# ssslidar_v1_0_main_board.net
KiCad netlist of a schematic drawn in EAGLE
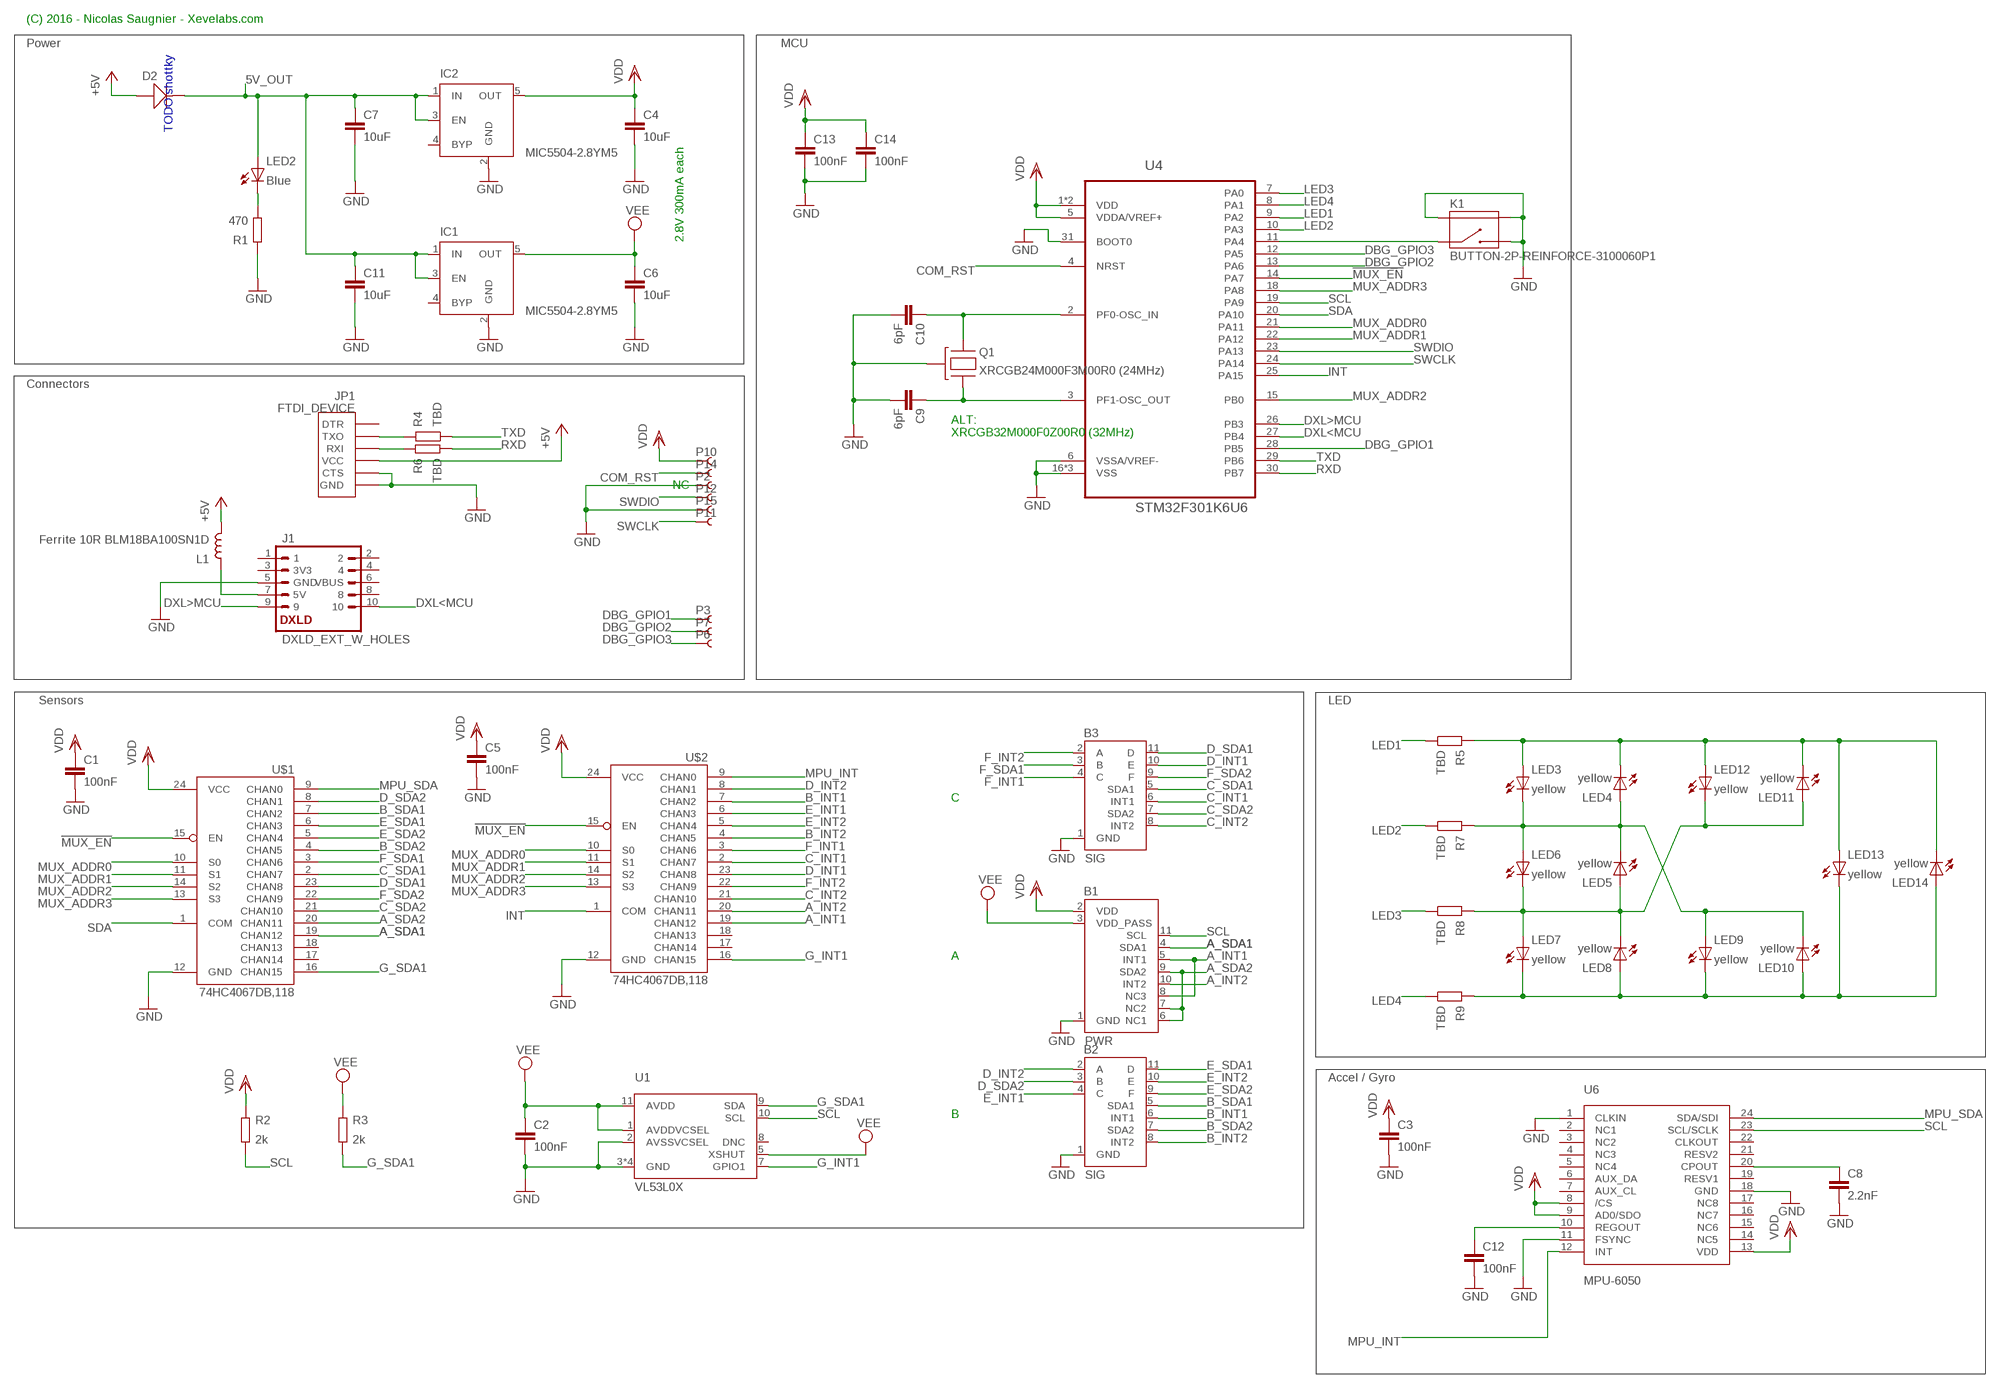
[diagram p0: schematic, sheet 1]

(export (version "E")
  (design (tool "Eeschema 10.0.6"))
  (components
    (comp (ref "B1")
      (value "PWR")
      (footprint "eagle-import:BLADE")
      (libsource (lib "eagle-import") (part "BLADE_PWR_BOTTOM"))
    )
    (comp (ref "B2")
      (value "SIG")
      (footprint "eagle-import:BLADE")
      (libsource (lib "eagle-import") (part "BLADE_SIG_BOTTOM"))
    )
    (comp (ref "B3")
      (value "SIG")
      (footprint "eagle-import:BLADE")
      (libsource (lib "eagle-import") (part "BLADE_SIG_BOTTOM"))
    )
    (comp (ref "C1")
      (value "100nF")
      (footprint "eagle-import:0402_N")
      (libsource (lib "eagle-import") (part "C0402"))
    )
    (comp (ref "C2")
      (value "100nF")
      (footprint "eagle-import:0402_N")
      (libsource (lib "eagle-import") (part "C0402"))
    )
    (comp (ref "C3")
      (value "100nF")
      (footprint "eagle-import:0402_N")
      (libsource (lib "eagle-import") (part "C0402"))
    )
    (comp (ref "C4")
      (value "10uF")
      (footprint "eagle-import:0805_N")
      (libsource (lib "eagle-import") (part "C0805"))
    )
    (comp (ref "C5")
      (value "100nF")
      (footprint "eagle-import:0402_N")
      (libsource (lib "eagle-import") (part "C0402"))
    )
    (comp (ref "C6")
      (value "10uF")
      (footprint "eagle-import:0805_N")
      (libsource (lib "eagle-import") (part "C0805"))
    )
    (comp (ref "C7")
      (value "10uF")
      (footprint "eagle-import:0805_N")
      (libsource (lib "eagle-import") (part "C0805"))
    )
    (comp (ref "C8")
      (value "2.2nF")
      (footprint "eagle-import:0402_N")
      (libsource (lib "eagle-import") (part "C0402"))
    )
    (comp (ref "C9")
      (value "6pF")
      (footprint "eagle-import:0402_N")
      (libsource (lib "eagle-import") (part "C0402"))
    )
    (comp (ref "C10")
      (value "6pF")
      (footprint "eagle-import:0402_N")
      (libsource (lib "eagle-import") (part "C0402"))
    )
    (comp (ref "C11")
      (value "10uF")
      (footprint "eagle-import:0805_N")
      (libsource (lib "eagle-import") (part "C0805"))
    )
    (comp (ref "C12")
      (value "100nF")
      (footprint "eagle-import:0402_N")
      (libsource (lib "eagle-import") (part "C0402"))
    )
    (comp (ref "C13")
      (value "100nF")
      (footprint "eagle-import:0402_N")
      (libsource (lib "eagle-import") (part "C0402"))
    )
    (comp (ref "C14")
      (value "100nF")
      (footprint "eagle-import:0402_N")
      (libsource (lib "eagle-import") (part "C0402"))
    )
    (comp (ref "D2")
      (value "D-SOD-123")
      (footprint "eagle-import:SOD123")
      (libsource (lib "eagle-import") (part "D-SOD-123"))
    )
    (comp (ref "IC1")
      (value "MIC5504-2.8YM5")
      (footprint "eagle-import:SOT23-5")
      (libsource (lib "eagle-import") (part "MIC5219XX"))
    )
    (comp (ref "IC2")
      (value "MIC5504-2.8YM5")
      (footprint "eagle-import:SOT23-5")
      (libsource (lib "eagle-import") (part "MIC5219XX"))
    )
    (comp (ref "J1")
      (value "DXLD_EXT_W_HOLES")
      (footprint "eagle-import:DXLD_EXT_W_HOLES")
      (libsource (lib "eagle-import") (part "DXLD_EXT_W_HOLES"))
    )
    (comp (ref "JP1")
      (value "FTDI_DEVICE")
      (footprint "eagle-import:FTDI_DEVICE_SIDE")
      (libsource (lib "eagle-import") (part "FTDI_DEVICE"))
    )
    (comp (ref "K1")
      (value "BUTTON-2P-REINFORCE-3100060P1")
      (footprint "eagle-import:4P-SMD-7.0X3.5X3.5H-90D")
      (libsource (lib "eagle-import") (part "BUTTON-2P-REINFORCE-3100060P1"))
    )
    (comp (ref "L1")
      (value "Ferrite 10R BLM18BA100SN1D")
      (footprint "eagle-import:0603_N")
      (libsource (lib "eagle-import") (part "L0603"))
    )
    (comp (ref "LED2")
      (value "Blue")
      (footprint "eagle-import:D_0603_N")
      (libsource (lib "eagle-import") (part "LED0603"))
    )
    (comp (ref "LED3")
      (value "yellow")
      (footprint "eagle-import:D_0603_N")
      (libsource (lib "eagle-import") (part "LED0603"))
    )
    (comp (ref "LED4")
      (value "yellow")
      (footprint "eagle-import:D_0603_N")
      (libsource (lib "eagle-import") (part "LED0603"))
    )
    (comp (ref "LED5")
      (value "yellow")
      (footprint "eagle-import:D_0603_N")
      (libsource (lib "eagle-import") (part "LED0603"))
    )
    (comp (ref "LED6")
      (value "yellow")
      (footprint "eagle-import:D_0603_N")
      (libsource (lib "eagle-import") (part "LED0603"))
    )
    (comp (ref "LED7")
      (value "yellow")
      (footprint "eagle-import:D_0603_N")
      (libsource (lib "eagle-import") (part "LED0603"))
    )
    (comp (ref "LED8")
      (value "yellow")
      (footprint "eagle-import:D_0603_N")
      (libsource (lib "eagle-import") (part "LED0603"))
    )
    (comp (ref "LED9")
      (value "yellow")
      (footprint "eagle-import:D_0603_N")
      (libsource (lib "eagle-import") (part "LED0603"))
    )
    (comp (ref "LED10")
      (value "yellow")
      (footprint "eagle-import:D_0603_N")
      (libsource (lib "eagle-import") (part "LED0603"))
    )
    (comp (ref "LED11")
      (value "yellow")
      (footprint "eagle-import:D_0603_N")
      (libsource (lib "eagle-import") (part "LED0603"))
    )
    (comp (ref "LED12")
      (value "yellow")
      (footprint "eagle-import:D_0603_N")
      (libsource (lib "eagle-import") (part "LED0603"))
    )
    (comp (ref "LED13")
      (value "yellow")
      (footprint "eagle-import:D_0603_N")
      (libsource (lib "eagle-import") (part "LED0603"))
    )
    (comp (ref "LED14")
      (value "yellow")
      (footprint "eagle-import:D_0603_N")
      (libsource (lib "eagle-import") (part "LED0603"))
    )
    (comp (ref "P2")
      (value "PIN_SMD_1X1.6")
      (footprint "eagle-import:PIN_SMD_1X1.6")
      (libsource (lib "eagle-import") (part "PIN_SMD_1X1.6"))
    )
    (comp (ref "P3")
      (value "PIN_SMD_1X1")
      (footprint "eagle-import:PIN_SMD_1X1")
      (libsource (lib "eagle-import") (part "PIN_SMD_1X1"))
    )
    (comp (ref "P6")
      (value "PIN_SMD_1X1")
      (footprint "eagle-import:PIN_SMD_1X1")
      (libsource (lib "eagle-import") (part "PIN_SMD_1X1"))
    )
    (comp (ref "P7")
      (value "PIN_SMD_1X1")
      (footprint "eagle-import:PIN_SMD_1X1")
      (libsource (lib "eagle-import") (part "PIN_SMD_1X1"))
    )
    (comp (ref "P10")
      (value "PIN_SMD_1X1.6")
      (footprint "eagle-import:PIN_SMD_1X1.6")
      (libsource (lib "eagle-import") (part "PIN_SMD_1X1.6"))
    )
    (comp (ref "P11")
      (value "PIN_SMD_1X1.6")
      (footprint "eagle-import:PIN_SMD_1X1.6")
      (libsource (lib "eagle-import") (part "PIN_SMD_1X1.6"))
    )
    (comp (ref "P12")
      (value "PIN_SMD_1X1.6")
      (footprint "eagle-import:PIN_SMD_1X1.6")
      (libsource (lib "eagle-import") (part "PIN_SMD_1X1.6"))
    )
    (comp (ref "P14")
      (value "PIN_SMD_1X1.6")
      (footprint "eagle-import:PIN_SMD_1X1.6")
      (libsource (lib "eagle-import") (part "PIN_SMD_1X1.6"))
    )
    (comp (ref "P15")
      (value "PIN_SMD_1X1.6")
      (footprint "eagle-import:PIN_SMD_1X1.6")
      (libsource (lib "eagle-import") (part "PIN_SMD_1X1.6"))
    )
    (comp (ref "Q1")
      (value "XRCGB24M000F3M00R0 (24MHz)")
      (footprint "eagle-import:CRYSTAL_2.0X1.6_4P")
      (libsource (lib "eagle-import") (part "CRYSTAL_W/BODY-2.0X1.6"))
    )
    (comp (ref "R1")
      (value "470")
      (footprint "eagle-import:0402_N")
      (libsource (lib "eagle-import") (part "R0402"))
    )
    (comp (ref "R2")
      (value "2k")
      (footprint "eagle-import:0402_N")
      (libsource (lib "eagle-import") (part "R0402"))
    )
    (comp (ref "R3")
      (value "2k")
      (footprint "eagle-import:0402_N")
      (libsource (lib "eagle-import") (part "R0402"))
    )
    (comp (ref "R4")
      (value "TBD")
      (footprint "eagle-import:0402_N")
      (libsource (lib "eagle-import") (part "R0402"))
    )
    (comp (ref "R5")
      (value "TBD")
      (footprint "eagle-import:0402_N")
      (libsource (lib "eagle-import") (part "R0402"))
    )
    (comp (ref "R6")
      (value "TBD")
      (footprint "eagle-import:0402_N")
      (libsource (lib "eagle-import") (part "R0402"))
    )
    (comp (ref "R7")
      (value "TBD")
      (footprint "eagle-import:0402_N")
      (libsource (lib "eagle-import") (part "R0402"))
    )
    (comp (ref "R8")
      (value "TBD")
      (footprint "eagle-import:0402_N")
      (libsource (lib "eagle-import") (part "R0402"))
    )
    (comp (ref "R9")
      (value "TBD")
      (footprint "eagle-import:0402_N")
      (libsource (lib "eagle-import") (part "R0402"))
    )
    (comp (ref "U$1")
      (value "74HC4067DB,118")
      (footprint "eagle-import:SSOP24")
      (libsource (lib "eagle-import") (part "MUX-74HC4067SMD"))
    )
    (comp (ref "U$2")
      (value "74HC4067DB,118")
      (footprint "eagle-import:SSOP24")
      (libsource (lib "eagle-import") (part "MUX-74HC4067SMD"))
    )
    (comp (ref "U1")
      (value "VL53L0X")
      (footprint "eagle-import:VL53L0X")
      (libsource (lib "eagle-import") (part "VL53L0X"))
    )
    (comp (ref "U4")
      (value "STM32F301K6U6")
      (footprint "eagle-import:QFN50P500X500X60-33N")
      (fields (field (name "MPN") "STM32F050K4U6A"))
      (libsource (lib "eagle-import") (part "STM32F301K6U6"))
    )
    (comp (ref "U6")
      (value "MPU-6050")
      (footprint "eagle-import:QFN-24")
      (libsource (lib "eagle-import") (part "MPU-6000"))
    )
  )
  (nets
    (net (code "1") (name "+5V") (class "Default")
      (node (ref "D2") (pin "+") (pinfunction "+_+") (pintype "passive"))
      (node (ref "JP1") (pin "P$4") (pinfunction "VCC_P$4") (pintype "bidirectional"))
      (node (ref "L1") (pin "2") (pinfunction "2_2") (pintype "passive"))
    )
    (net (code "2") (name "/5V_OUT") (class "Default")
      (node (ref "C11") (pin "1") (pinfunction "1_1") (pintype "passive"))
      (node (ref "C7") (pin "1") (pinfunction "1_1") (pintype "passive"))
      (node (ref "D2") (pin "-") (pinfunction "-_-") (pintype "passive"))
      (node (ref "IC1") (pin "1") (pinfunction "IN_1") (pintype "input"))
      (node (ref "IC1") (pin "3") (pinfunction "EN_3") (pintype "input"))
      (node (ref "IC2") (pin "1") (pinfunction "IN_1") (pintype "input"))
      (node (ref "IC2") (pin "3") (pinfunction "EN_3") (pintype "input"))
      (node (ref "LED2") (pin "A") (pinfunction "A_A") (pintype "passive"))
    )
    (net (code "3") (name "/A_INT1") (class "Default")
      (node (ref "B1") (pin "5") (pinfunction "INT1_5") (pintype "bidirectional"))
      (node (ref "B1") (pin "8") (pinfunction "NC3_8") (pintype "bidirectional"))
      (node (ref "U$2") (pin "19") (pinfunction "CHAN12_19") (pintype "bidirectional"))
    )
    (net (code "4") (name "/A_INT2") (class "Default")
      (node (ref "B1") (pin "10") (pinfunction "INT2_10") (pintype "bidirectional"))
      (node (ref "U$2") (pin "20") (pinfunction "CHAN11_20") (pintype "bidirectional"))
    )
    (net (code "5") (name "/A_SDA1") (class "Default")
      (node (ref "B1") (pin "4") (pinfunction "SDA1_4") (pintype "bidirectional"))
      (node (ref "U$1") (pin "19") (pinfunction "CHAN12_19") (pintype "bidirectional"))
    )
    (net (code "6") (name "/A_SDA2") (class "Default")
      (node (ref "B1") (pin "6") (pinfunction "NC1_6") (pintype "bidirectional"))
      (node (ref "B1") (pin "7") (pinfunction "NC2_7") (pintype "bidirectional"))
      (node (ref "B1") (pin "9") (pinfunction "SDA2_9") (pintype "bidirectional"))
      (node (ref "U$1") (pin "20") (pinfunction "CHAN11_20") (pintype "bidirectional"))
    )
    (net (code "7") (name "/B_INT1") (class "Default")
      (node (ref "B2") (pin "6") (pinfunction "INT1_6") (pintype "bidirectional"))
      (node (ref "U$2") (pin "7") (pinfunction "CHAN2_7") (pintype "bidirectional"))
    )
    (net (code "8") (name "/B_INT2") (class "Default")
      (node (ref "B2") (pin "8") (pinfunction "INT2_8") (pintype "bidirectional"))
      (node (ref "U$2") (pin "4") (pinfunction "CHAN5_4") (pintype "bidirectional"))
    )
    (net (code "9") (name "/B_SDA1") (class "Default")
      (node (ref "B2") (pin "5") (pinfunction "SDA1_5") (pintype "bidirectional"))
      (node (ref "U$1") (pin "7") (pinfunction "CHAN2_7") (pintype "bidirectional"))
    )
    (net (code "10") (name "/B_SDA2") (class "Default")
      (node (ref "B2") (pin "7") (pinfunction "SDA2_7") (pintype "bidirectional"))
      (node (ref "U$1") (pin "4") (pinfunction "CHAN5_4") (pintype "bidirectional"))
    )
    (net (code "11") (name "/COM_RST") (class "Default")
      (node (ref "P14") (pin "PIN") (pinfunction "1_PIN") (pintype "bidirectional"))
      (node (ref "U4") (pin "4") (pinfunction "NRST_4") (pintype "bidirectional"))
    )
    (net (code "12") (name "/C_INT1") (class "Default")
      (node (ref "B3") (pin "6") (pinfunction "INT1_6") (pintype "bidirectional"))
      (node (ref "U$2") (pin "2") (pinfunction "CHAN7_2") (pintype "bidirectional"))
    )
    (net (code "13") (name "/C_INT2") (class "Default")
      (node (ref "B3") (pin "8") (pinfunction "INT2_8") (pintype "bidirectional"))
      (node (ref "U$2") (pin "21") (pinfunction "CHAN10_21") (pintype "bidirectional"))
    )
    (net (code "14") (name "/C_SDA1") (class "Default")
      (node (ref "B3") (pin "5") (pinfunction "SDA1_5") (pintype "bidirectional"))
      (node (ref "U$1") (pin "2") (pinfunction "CHAN7_2") (pintype "bidirectional"))
    )
    (net (code "15") (name "/C_SDA2") (class "Default")
      (node (ref "B3") (pin "7") (pinfunction "SDA2_7") (pintype "bidirectional"))
      (node (ref "U$1") (pin "21") (pinfunction "CHAN10_21") (pintype "bidirectional"))
    )
    (net (code "16") (name "/DBG_GPIO1") (class "Default")
      (node (ref "P3") (pin "P$1") (pinfunction "1_P$1") (pintype "bidirectional"))
      (node (ref "U4") (pin "28") (pinfunction "PB5_28") (pintype "bidirectional"))
    )
    (net (code "17") (name "/DBG_GPIO2") (class "Default")
      (node (ref "P7") (pin "P$1") (pinfunction "1_P$1") (pintype "bidirectional"))
      (node (ref "U4") (pin "13") (pinfunction "PA6_13") (pintype "bidirectional"))
    )
    (net (code "18") (name "/DBG_GPIO3") (class "Default")
      (node (ref "P6") (pin "P$1") (pinfunction "1_P$1") (pintype "bidirectional"))
      (node (ref "U4") (pin "12") (pinfunction "PA5_12") (pintype "bidirectional"))
    )
    (net (code "19") (name "/DXL<MCU") (class "Default")
      (node (ref "J1") (pin "10") (pinfunction "10_10") (pintype "passive"))
      (node (ref "U4") (pin "27") (pinfunction "PB4_27") (pintype "bidirectional"))
    )
    (net (code "20") (name "/DXL>MCU") (class "Default")
      (node (ref "J1") (pin "9") (pinfunction "9_9") (pintype "passive"))
      (node (ref "U4") (pin "26") (pinfunction "PB3_26") (pintype "bidirectional"))
    )
    (net (code "21") (name "/D_INT1") (class "Default")
      (node (ref "B3") (pin "10") (pinfunction "E_10") (pintype "bidirectional"))
      (node (ref "U$2") (pin "23") (pinfunction "CHAN8_23") (pintype "bidirectional"))
    )
    (net (code "22") (name "/D_INT2") (class "Default")
      (node (ref "B2") (pin "2") (pinfunction "A_2") (pintype "bidirectional"))
      (node (ref "U$2") (pin "8") (pinfunction "CHAN1_8") (pintype "bidirectional"))
    )
    (net (code "23") (name "/D_SDA1") (class "Default")
      (node (ref "B3") (pin "11") (pinfunction "D_11") (pintype "bidirectional"))
      (node (ref "U$1") (pin "23") (pinfunction "CHAN8_23") (pintype "bidirectional"))
    )
    (net (code "24") (name "/D_SDA2") (class "Default")
      (node (ref "B2") (pin "3") (pinfunction "B_3") (pintype "bidirectional"))
      (node (ref "U$1") (pin "8") (pinfunction "CHAN1_8") (pintype "bidirectional"))
    )
    (net (code "25") (name "/E_INT1") (class "Default")
      (node (ref "B2") (pin "4") (pinfunction "C_4") (pintype "bidirectional"))
      (node (ref "U$2") (pin "6") (pinfunction "CHAN3_6") (pintype "bidirectional"))
    )
    (net (code "26") (name "/E_INT2") (class "Default")
      (node (ref "B2") (pin "10") (pinfunction "E_10") (pintype "bidirectional"))
      (node (ref "U$2") (pin "5") (pinfunction "CHAN4_5") (pintype "bidirectional"))
    )
    (net (code "27") (name "/E_SDA1") (class "Default")
      (node (ref "B2") (pin "11") (pinfunction "D_11") (pintype "bidirectional"))
      (node (ref "U$1") (pin "6") (pinfunction "CHAN3_6") (pintype "bidirectional"))
    )
    (net (code "28") (name "/E_SDA2") (class "Default")
      (node (ref "B2") (pin "9") (pinfunction "F_9") (pintype "bidirectional"))
      (node (ref "U$1") (pin "5") (pinfunction "CHAN4_5") (pintype "bidirectional"))
    )
    (net (code "29") (name "/F_INT1") (class "Default")
      (node (ref "B3") (pin "4") (pinfunction "C_4") (pintype "bidirectional"))
      (node (ref "U$2") (pin "3") (pinfunction "CHAN6_3") (pintype "bidirectional"))
    )
    (net (code "30") (name "/F_INT2") (class "Default")
      (node (ref "B3") (pin "2") (pinfunction "A_2") (pintype "bidirectional"))
      (node (ref "U$2") (pin "22") (pinfunction "CHAN9_22") (pintype "bidirectional"))
    )
    (net (code "31") (name "/F_SDA1") (class "Default")
      (node (ref "B3") (pin "3") (pinfunction "B_3") (pintype "bidirectional"))
      (node (ref "U$1") (pin "3") (pinfunction "CHAN6_3") (pintype "bidirectional"))
    )
    (net (code "32") (name "/F_SDA2") (class "Default")
      (node (ref "B3") (pin "9") (pinfunction "F_9") (pintype "bidirectional"))
      (node (ref "U$1") (pin "22") (pinfunction "CHAN9_22") (pintype "bidirectional"))
    )
    (net (code "33") (name "/G_INT1") (class "Default")
      (node (ref "U$2") (pin "16") (pinfunction "CHAN15_16") (pintype "bidirectional"))
      (node (ref "U1") (pin "7") (pinfunction "GPIO1_7") (pintype "bidirectional"))
    )
    (net (code "34") (name "/G_SDA1") (class "Default")
      (node (ref "R3") (pin "1") (pinfunction "1_1") (pintype "passive"))
      (node (ref "U$1") (pin "16") (pinfunction "CHAN15_16") (pintype "bidirectional"))
      (node (ref "U1") (pin "9") (pinfunction "SDA_9") (pintype "bidirectional"))
    )
    (net (code "35") (name "/INT") (class "Default")
      (node (ref "U$2") (pin "1") (pinfunction "COM_1") (pintype "bidirectional"))
      (node (ref "U4") (pin "25") (pinfunction "PA15_25") (pintype "bidirectional"))
    )
    (net (code "36") (name "/LED1") (class "Default")
      (node (ref "R5") (pin "1") (pinfunction "1_1") (pintype "passive"))
      (node (ref "U4") (pin "9") (pinfunction "PA2_9") (pintype "bidirectional"))
    )
    (net (code "37") (name "/LED2") (class "Default")
      (node (ref "R7") (pin "1") (pinfunction "1_1") (pintype "passive"))
      (node (ref "U4") (pin "10") (pinfunction "PA3_10") (pintype "bidirectional"))
    )
    (net (code "38") (name "/LED3") (class "Default")
      (node (ref "R8") (pin "1") (pinfunction "1_1") (pintype "passive"))
      (node (ref "U4") (pin "7") (pinfunction "PA0_7") (pintype "bidirectional"))
    )
    (net (code "39") (name "/LED4") (class "Default")
      (node (ref "R9") (pin "1") (pinfunction "1_1") (pintype "passive"))
      (node (ref "U4") (pin "8") (pinfunction "PA1_8") (pintype "bidirectional"))
    )
    (net (code "40") (name "/MPU_INT") (class "Default")
      (node (ref "U$2") (pin "9") (pinfunction "CHAN0_9") (pintype "bidirectional"))
      (node (ref "U6") (pin "12") (pinfunction "INT_12") (pintype "bidirectional"))
    )
    (net (code "41") (name "/MPU_SDA") (class "Default")
      (node (ref "U$1") (pin "9") (pinfunction "CHAN0_9") (pintype "bidirectional"))
      (node (ref "U6") (pin "24") (pinfunction "SDA/SDI_24") (pintype "bidirectional"))
    )
    (net (code "42") (name "/MUX_ADDR0") (class "Default")
      (node (ref "U$1") (pin "10") (pinfunction "S0_10") (pintype "input"))
      (node (ref "U$2") (pin "10") (pinfunction "S0_10") (pintype "input"))
      (node (ref "U4") (pin "21") (pinfunction "PA11_21") (pintype "bidirectional"))
    )
    (net (code "43") (name "/MUX_ADDR1") (class "Default")
      (node (ref "U$1") (pin "11") (pinfunction "S1_11") (pintype "input"))
      (node (ref "U$2") (pin "11") (pinfunction "S1_11") (pintype "input"))
      (node (ref "U4") (pin "22") (pinfunction "PA12_22") (pintype "bidirectional"))
    )
    (net (code "44") (name "/MUX_ADDR2") (class "Default")
      (node (ref "U$1") (pin "14") (pinfunction "S2_14") (pintype "input"))
      (node (ref "U$2") (pin "14") (pinfunction "S2_14") (pintype "input"))
      (node (ref "U4") (pin "15") (pinfunction "PB0_15") (pintype "bidirectional"))
    )
    (net (code "45") (name "/MUX_ADDR3") (class "Default")
      (node (ref "U$1") (pin "13") (pinfunction "S3_13") (pintype "input"))
      (node (ref "U$2") (pin "13") (pinfunction "S3_13") (pintype "input"))
      (node (ref "U4") (pin "18") (pinfunction "PA8_18") (pintype "bidirectional"))
    )
    (net (code "46") (name "/RXD") (class "Default")
      (node (ref "R6") (pin "1") (pinfunction "1_1") (pintype "passive"))
      (node (ref "U4") (pin "30") (pinfunction "PB7_30") (pintype "bidirectional"))
    )
    (net (code "47") (name "/SCL") (class "Default")
      (node (ref "B1") (pin "11") (pinfunction "SCL_11") (pintype "bidirectional"))
      (node (ref "R2") (pin "1") (pinfunction "1_1") (pintype "passive"))
      (node (ref "U1") (pin "10") (pinfunction "SCL_10") (pintype "bidirectional"))
      (node (ref "U4") (pin "19") (pinfunction "PA9_19") (pintype "bidirectional"))
      (node (ref "U6") (pin "23") (pinfunction "SCL/SCLK_23") (pintype "bidirectional"))
    )
    (net (code "48") (name "/SDA") (class "Default")
      (node (ref "U$1") (pin "1") (pinfunction "COM_1") (pintype "bidirectional"))
      (node (ref "U4") (pin "20") (pinfunction "PA10_20") (pintype "bidirectional"))
    )
    (net (code "49") (name "/SWCLK") (class "Default")
      (node (ref "P11") (pin "PIN") (pinfunction "1_PIN") (pintype "bidirectional"))
      (node (ref "U4") (pin "24") (pinfunction "PA14_24") (pintype "bidirectional"))
    )
    (net (code "50") (name "/SWDIO") (class "Default")
      (node (ref "P12") (pin "PIN") (pinfunction "1_PIN") (pintype "bidirectional"))
      (node (ref "U4") (pin "23") (pinfunction "PA13_23") (pintype "bidirectional"))
    )
    (net (code "51") (name "/TXD") (class "Default")
      (node (ref "R4") (pin "1") (pinfunction "1_1") (pintype "passive"))
      (node (ref "U4") (pin "29") (pinfunction "PB6_29") (pintype "bidirectional"))
    )
    (net (code "52") (name "/~{MUX_EN}") (class "Default")
      (node (ref "U$1") (pin "15") (pinfunction "EN_15") (pintype "input"))
      (node (ref "U$2") (pin "15") (pinfunction "EN_15") (pintype "input"))
      (node (ref "U4") (pin "14") (pinfunction "PA7_14") (pintype "bidirectional"))
    )
    (net (code "53") (name "GND") (class "Default")
      (node (ref "B1") (pin "1") (pinfunction "GND_1") (pintype "bidirectional"))
      (node (ref "B2") (pin "1") (pinfunction "GND_1") (pintype "bidirectional"))
      (node (ref "B3") (pin "1") (pinfunction "GND_1") (pintype "bidirectional"))
      (node (ref "C1") (pin "2") (pinfunction "2_2") (pintype "passive"))
      (node (ref "C10") (pin "2") (pinfunction "2_2") (pintype "passive"))
      (node (ref "C11") (pin "2") (pinfunction "2_2") (pintype "passive"))
      (node (ref "C12") (pin "2") (pinfunction "2_2") (pintype "passive"))
      (node (ref "C13") (pin "2") (pinfunction "2_2") (pintype "passive"))
      (node (ref "C14") (pin "2") (pinfunction "2_2") (pintype "passive"))
      (node (ref "C2") (pin "2") (pinfunction "2_2") (pintype "passive"))
      (node (ref "C3") (pin "2") (pinfunction "2_2") (pintype "passive"))
      (node (ref "C4") (pin "2") (pinfunction "2_2") (pintype "passive"))
      (node (ref "C5") (pin "2") (pinfunction "2_2") (pintype "passive"))
      (node (ref "C6") (pin "2") (pinfunction "2_2") (pintype "passive"))
      (node (ref "C7") (pin "2") (pinfunction "2_2") (pintype "passive"))
      (node (ref "C8") (pin "2") (pinfunction "2_2") (pintype "passive"))
      (node (ref "C9") (pin "2") (pinfunction "2_2") (pintype "passive"))
      (node (ref "IC1") (pin "2") (pinfunction "GND_2") (pintype "power_in"))
      (node (ref "IC2") (pin "2") (pinfunction "GND_2") (pintype "power_in"))
      (node (ref "J1") (pin "5") (pinfunction "GND_5") (pintype "passive"))
      (node (ref "JP1") (pin "P$5") (pinfunction "CTS_P$5") (pintype "bidirectional"))
      (node (ref "JP1") (pin "P$6") (pinfunction "GND_P$6") (pintype "bidirectional"))
      (node (ref "K1") (pin "2") (pinfunction "2_2") (pintype "bidirectional"))
      (node (ref "K1") (pin "S1") (pinfunction "S1_S1") (pintype "bidirectional"))
      (node (ref "K1") (pin "S2") (pinfunction "S2_S2") (pintype "bidirectional"))
      (node (ref "P15") (pin "PIN") (pinfunction "1_PIN") (pintype "bidirectional"))
      (node (ref "P2") (pin "PIN") (pinfunction "1_PIN") (pintype "bidirectional"))
      (node (ref "Q1") (pin "2") (pinfunction "GND_2") (pintype "passive"))
      (node (ref "Q1") (pin "4") (pinfunction "GND_4") (pintype "passive"))
      (node (ref "R1") (pin "2") (pinfunction "2_2") (pintype "passive"))
      (node (ref "U$1") (pin "12") (pinfunction "GND_12") (pintype "bidirectional"))
      (node (ref "U$2") (pin "12") (pinfunction "GND_12") (pintype "bidirectional"))
      (node (ref "U1") (pin "12") (pinfunction "GND_12") (pintype "bidirectional"))
      (node (ref "U1") (pin "2") (pinfunction "AVSSVCSEL_2") (pintype "bidirectional"))
      (node (ref "U1") (pin "3") (pinfunction "GND_3") (pintype "bidirectional"))
      (node (ref "U1") (pin "4") (pinfunction "GND_4") (pintype "bidirectional"))
      (node (ref "U1") (pin "6") (pinfunction "GND_6") (pintype "bidirectional"))
      (node (ref "U4") (pin "16") (pinfunction "VSS_16") (pintype "bidirectional"))
      (node (ref "U4") (pin "31") (pinfunction "BOOT0_31") (pintype "input"))
      (node (ref "U4") (pin "32") (pinfunction "VSS_32") (pintype "bidirectional"))
      (node (ref "U4") (pin "33") (pinfunction "VSS_33") (pintype "bidirectional"))
      (node (ref "U4") (pin "6") (pinfunction "VSSA/VREF-_6") (pintype "passive"))
      (node (ref "U6") (pin "1") (pinfunction "CLKIN_1") (pintype "bidirectional"))
      (node (ref "U6") (pin "11") (pinfunction "FSYNC_11") (pintype "bidirectional"))
      (node (ref "U6") (pin "18") (pinfunction "GND_18") (pintype "bidirectional"))
    )
    (net (code "54") (name "Net-(J1-5V)") (class "Default")
      (node (ref "J1") (pin "7") (pinfunction "5V_7") (pintype "passive"))
      (node (ref "L1") (pin "1") (pinfunction "1_1") (pintype "passive"))
    )
    (net (code "55") (name "Net-(JP1-RXI)") (class "Default")
      (node (ref "JP1") (pin "P$3") (pinfunction "RXI_P$3") (pintype "bidirectional"))
      (node (ref "R6") (pin "2") (pinfunction "2_2") (pintype "passive"))
    )
    (net (code "56") (name "Net-(JP1-TXO)") (class "Default")
      (node (ref "JP1") (pin "P$2") (pinfunction "TXO_P$2") (pintype "bidirectional"))
      (node (ref "R4") (pin "2") (pinfunction "2_2") (pintype "passive"))
    )
    (net (code "57") (name "Net-(LED2-PadC)") (class "Default")
      (node (ref "LED2") (pin "C") (pinfunction "C_C") (pintype "passive"))
      (node (ref "R1") (pin "1") (pinfunction "1_1") (pintype "passive"))
    )
    (net (code "58") (name "Net-(LED10-PadA)") (class "Default")
      (node (ref "LED10") (pin "A") (pinfunction "A_A") (pintype "passive"))
      (node (ref "LED13") (pin "C") (pinfunction "C_C") (pintype "passive"))
      (node (ref "LED14") (pin "A") (pinfunction "A_A") (pintype "passive"))
      (node (ref "LED7") (pin "C") (pinfunction "C_C") (pintype "passive"))
      (node (ref "LED8") (pin "A") (pinfunction "A_A") (pintype "passive"))
      (node (ref "LED9") (pin "C") (pinfunction "C_C") (pintype "passive"))
      (node (ref "R9") (pin "2") (pinfunction "2_2") (pintype "passive"))
    )
    (net (code "59") (name "Net-(LED10-PadC)") (class "Default")
      (node (ref "LED10") (pin "C") (pinfunction "C_C") (pintype "passive"))
      (node (ref "LED3") (pin "C") (pinfunction "C_C") (pintype "passive"))
      (node (ref "LED4") (pin "A") (pinfunction "A_A") (pintype "passive"))
      (node (ref "LED5") (pin "C") (pinfunction "C_C") (pintype "passive"))
      (node (ref "LED6") (pin "A") (pinfunction "A_A") (pintype "passive"))
      (node (ref "LED9") (pin "A") (pinfunction "A_A") (pintype "passive"))
      (node (ref "R7") (pin "2") (pinfunction "2_2") (pintype "passive"))
    )
    (net (code "60") (name "Net-(LED11-PadA)") (class "Default")
      (node (ref "LED11") (pin "A") (pinfunction "A_A") (pintype "passive"))
      (node (ref "LED12") (pin "C") (pinfunction "C_C") (pintype "passive"))
      (node (ref "LED5") (pin "A") (pinfunction "A_A") (pintype "passive"))
      (node (ref "LED6") (pin "C") (pinfunction "C_C") (pintype "passive"))
      (node (ref "LED7") (pin "A") (pinfunction "A_A") (pintype "passive"))
      (node (ref "LED8") (pin "C") (pinfunction "C_C") (pintype "passive"))
      (node (ref "R8") (pin "2") (pinfunction "2_2") (pintype "passive"))
    )
    (net (code "61") (name "Net-(LED11-PadC)") (class "Default")
      (node (ref "LED11") (pin "C") (pinfunction "C_C") (pintype "passive"))
      (node (ref "LED12") (pin "A") (pinfunction "A_A") (pintype "passive"))
      (node (ref "LED13") (pin "A") (pinfunction "A_A") (pintype "passive"))
      (node (ref "LED14") (pin "C") (pinfunction "C_C") (pintype "passive"))
      (node (ref "LED3") (pin "A") (pinfunction "A_A") (pintype "passive"))
      (node (ref "LED4") (pin "C") (pinfunction "C_C") (pintype "passive"))
      (node (ref "R5") (pin "2") (pinfunction "2_2") (pintype "passive"))
    )
    (net (code "62") (name "Net-(Q1-P$1)") (class "Default")
      (node (ref "C10") (pin "1") (pinfunction "1_1") (pintype "passive"))
      (node (ref "Q1") (pin "1") (pinfunction "P$1_1") (pintype "passive"))
      (node (ref "U4") (pin "2") (pinfunction "PF0-OSC_IN_2") (pintype "bidirectional"))
    )
    (net (code "63") (name "Net-(Q1-P$2)") (class "Default")
      (node (ref "C9") (pin "1") (pinfunction "1_1") (pintype "passive"))
      (node (ref "Q1") (pin "3") (pinfunction "P$2_3") (pintype "passive"))
      (node (ref "U4") (pin "3") (pinfunction "PF1-OSC_OUT_3") (pintype "bidirectional"))
    )
    (net (code "64") (name "Net-(U4-PA4)") (class "Default")
      (node (ref "K1") (pin "1") (pinfunction "1_1") (pintype "bidirectional"))
      (node (ref "U4") (pin "11") (pinfunction "PA4_11") (pintype "bidirectional"))
    )
    (net (code "65") (name "Net-(U6-CPOUT)") (class "Default")
      (node (ref "C8") (pin "1") (pinfunction "1_1") (pintype "passive"))
      (node (ref "U6") (pin "20") (pinfunction "CPOUT_20") (pintype "bidirectional"))
    )
    (net (code "66") (name "Net-(U6-REGOUT)") (class "Default")
      (node (ref "C12") (pin "1") (pinfunction "1_1") (pintype "passive"))
      (node (ref "U6") (pin "10") (pinfunction "REGOUT_10") (pintype "bidirectional"))
    )
    (net (code "67") (name "VDD") (class "Default")
      (node (ref "B1") (pin "2") (pinfunction "VDD_2") (pintype "bidirectional"))
      (node (ref "C1") (pin "1") (pinfunction "1_1") (pintype "passive"))
      (node (ref "C13") (pin "1") (pinfunction "1_1") (pintype "passive"))
      (node (ref "C14") (pin "1") (pinfunction "1_1") (pintype "passive"))
      (node (ref "C3") (pin "1") (pinfunction "1_1") (pintype "passive"))
      (node (ref "C4") (pin "1") (pinfunction "1_1") (pintype "passive"))
      (node (ref "C5") (pin "1") (pinfunction "1_1") (pintype "passive"))
      (node (ref "IC2") (pin "5") (pinfunction "OUT_5") (pintype "output"))
      (node (ref "P10") (pin "PIN") (pinfunction "1_PIN") (pintype "bidirectional"))
      (node (ref "R2") (pin "2") (pinfunction "2_2") (pintype "passive"))
      (node (ref "U$1") (pin "24") (pinfunction "VCC_24") (pintype "bidirectional"))
      (node (ref "U$2") (pin "24") (pinfunction "VCC_24") (pintype "bidirectional"))
      (node (ref "U4") (pin "1") (pinfunction "VDD_1") (pintype "power_in"))
      (node (ref "U4") (pin "17") (pinfunction "VDD_17") (pintype "power_in"))
      (node (ref "U4") (pin "5") (pinfunction "VDDA/VREF+_5") (pintype "power_in"))
      (node (ref "U6") (pin "13") (pinfunction "VDD_13") (pintype "bidirectional"))
      (node (ref "U6") (pin "8") (pinfunction "/CS_8") (pintype "bidirectional"))
      (node (ref "U6") (pin "9") (pinfunction "AD0/SDO_9") (pintype "bidirectional"))
    )
    (net (code "68") (name "VEE") (class "Default")
      (node (ref "B1") (pin "3") (pinfunction "VDD_PASS_3") (pintype "bidirectional"))
      (node (ref "C2") (pin "1") (pinfunction "1_1") (pintype "passive"))
      (node (ref "C6") (pin "1") (pinfunction "1_1") (pintype "passive"))
      (node (ref "IC1") (pin "5") (pinfunction "OUT_5") (pintype "output"))
      (node (ref "R3") (pin "2") (pinfunction "2_2") (pintype "passive"))
      (node (ref "U1") (pin "1") (pinfunction "AVDDVCSEL_1") (pintype "bidirectional"))
      (node (ref "U1") (pin "11") (pinfunction "AVDD_11") (pintype "bidirectional"))
      (node (ref "U1") (pin "5") (pinfunction "XSHUT_5") (pintype "bidirectional"))
    )
    (net (code "69") (name "unconnected-(IC1-BYP-Pad4)") (class "Default")
      (node (ref "IC1") (pin "4") (pinfunction "BYP_4") (pintype "passive"))
    )
    (net (code "70") (name "unconnected-(IC2-BYP-Pad4)") (class "Default")
      (node (ref "IC2") (pin "4") (pinfunction "BYP_4") (pintype "passive"))
    )
    (net (code "71") (name "unconnected-(J1-3V3-Pad3)") (class "Default")
      (node (ref "J1") (pin "3") (pinfunction "3V3_3") (pintype "passive"))
    )
    (net (code "72") (name "unconnected-(J1-Pad1)") (class "Default")
      (node (ref "J1") (pin "1") (pinfunction "1_1") (pintype "passive"))
    )
    (net (code "73") (name "unconnected-(J1-Pad2)") (class "Default")
      (node (ref "J1") (pin "2") (pinfunction "2_2") (pintype "passive"))
    )
    (net (code "74") (name "unconnected-(J1-Pad4)") (class "Default")
      (node (ref "J1") (pin "4") (pinfunction "4_4") (pintype "passive"))
    )
    (net (code "75") (name "unconnected-(J1-Pad8)") (class "Default")
      (node (ref "J1") (pin "8") (pinfunction "8_8") (pintype "passive"))
    )
    (net (code "76") (name "unconnected-(J1-VBUS-Pad6)") (class "Default")
      (node (ref "J1") (pin "6") (pinfunction "VBUS_6") (pintype "passive"))
    )
    (net (code "77") (name "unconnected-(JP1-DTR-PadP$1)") (class "Default")
      (node (ref "JP1") (pin "P$1") (pinfunction "DTR_P$1") (pintype "bidirectional"))
    )
    (net (code "78") (name "unconnected-(U$1-CHAN13-Pad18)") (class "Default")
      (node (ref "U$1") (pin "18") (pinfunction "CHAN13_18") (pintype "bidirectional"))
    )
    (net (code "79") (name "unconnected-(U$1-CHAN14-Pad17)") (class "Default")
      (node (ref "U$1") (pin "17") (pinfunction "CHAN14_17") (pintype "bidirectional"))
    )
    (net (code "80") (name "unconnected-(U$2-CHAN13-Pad18)") (class "Default")
      (node (ref "U$2") (pin "18") (pinfunction "CHAN13_18") (pintype "bidirectional"))
    )
    (net (code "81") (name "unconnected-(U$2-CHAN14-Pad17)") (class "Default")
      (node (ref "U$2") (pin "17") (pinfunction "CHAN14_17") (pintype "bidirectional"))
    )
    (net (code "82") (name "unconnected-(U1-DNC-Pad8)") (class "Default")
      (node (ref "U1") (pin "8") (pinfunction "DNC_8") (pintype "bidirectional"))
    )
    (net (code "83") (name "unconnected-(U6-AUX_CL-Pad7)") (class "Default")
      (node (ref "U6") (pin "7") (pinfunction "AUX_CL_7") (pintype "bidirectional"))
    )
    (net (code "84") (name "unconnected-(U6-AUX_DA-Pad6)") (class "Default")
      (node (ref "U6") (pin "6") (pinfunction "AUX_DA_6") (pintype "bidirectional"))
    )
    (net (code "85") (name "unconnected-(U6-CLKOUT-Pad22)") (class "Default")
      (node (ref "U6") (pin "22") (pinfunction "CLKOUT_22") (pintype "bidirectional"))
    )
    (net (code "86") (name "unconnected-(U6-NC1-Pad2)") (class "Default")
      (node (ref "U6") (pin "2") (pinfunction "NC1_2") (pintype "bidirectional"))
    )
    (net (code "87") (name "unconnected-(U6-NC2-Pad3)") (class "Default")
      (node (ref "U6") (pin "3") (pinfunction "NC2_3") (pintype "bidirectional"))
    )
    (net (code "88") (name "unconnected-(U6-NC3-Pad4)") (class "Default")
      (node (ref "U6") (pin "4") (pinfunction "NC3_4") (pintype "bidirectional"))
    )
    (net (code "89") (name "unconnected-(U6-NC4-Pad5)") (class "Default")
      (node (ref "U6") (pin "5") (pinfunction "NC4_5") (pintype "bidirectional"))
    )
    (net (code "90") (name "unconnected-(U6-NC5-Pad14)") (class "Default")
      (node (ref "U6") (pin "14") (pinfunction "NC5_14") (pintype "bidirectional"))
    )
    (net (code "91") (name "unconnected-(U6-NC6-Pad15)") (class "Default")
      (node (ref "U6") (pin "15") (pinfunction "NC6_15") (pintype "bidirectional"))
    )
    (net (code "92") (name "unconnected-(U6-NC7-Pad16)") (class "Default")
      (node (ref "U6") (pin "16") (pinfunction "NC7_16") (pintype "bidirectional"))
    )
    (net (code "93") (name "unconnected-(U6-NC8-Pad17)") (class "Default")
      (node (ref "U6") (pin "17") (pinfunction "NC8_17") (pintype "bidirectional"))
    )
    (net (code "94") (name "unconnected-(U6-RESV1-Pad19)") (class "Default")
      (node (ref "U6") (pin "19") (pinfunction "RESV1_19") (pintype "bidirectional"))
    )
    (net (code "95") (name "unconnected-(U6-RESV2-Pad21)") (class "Default")
      (node (ref "U6") (pin "21") (pinfunction "RESV2_21") (pintype "bidirectional"))
    )
  )
)
